# Sensor.net
KiCad netlist of a schematic drawn in Altium Designer
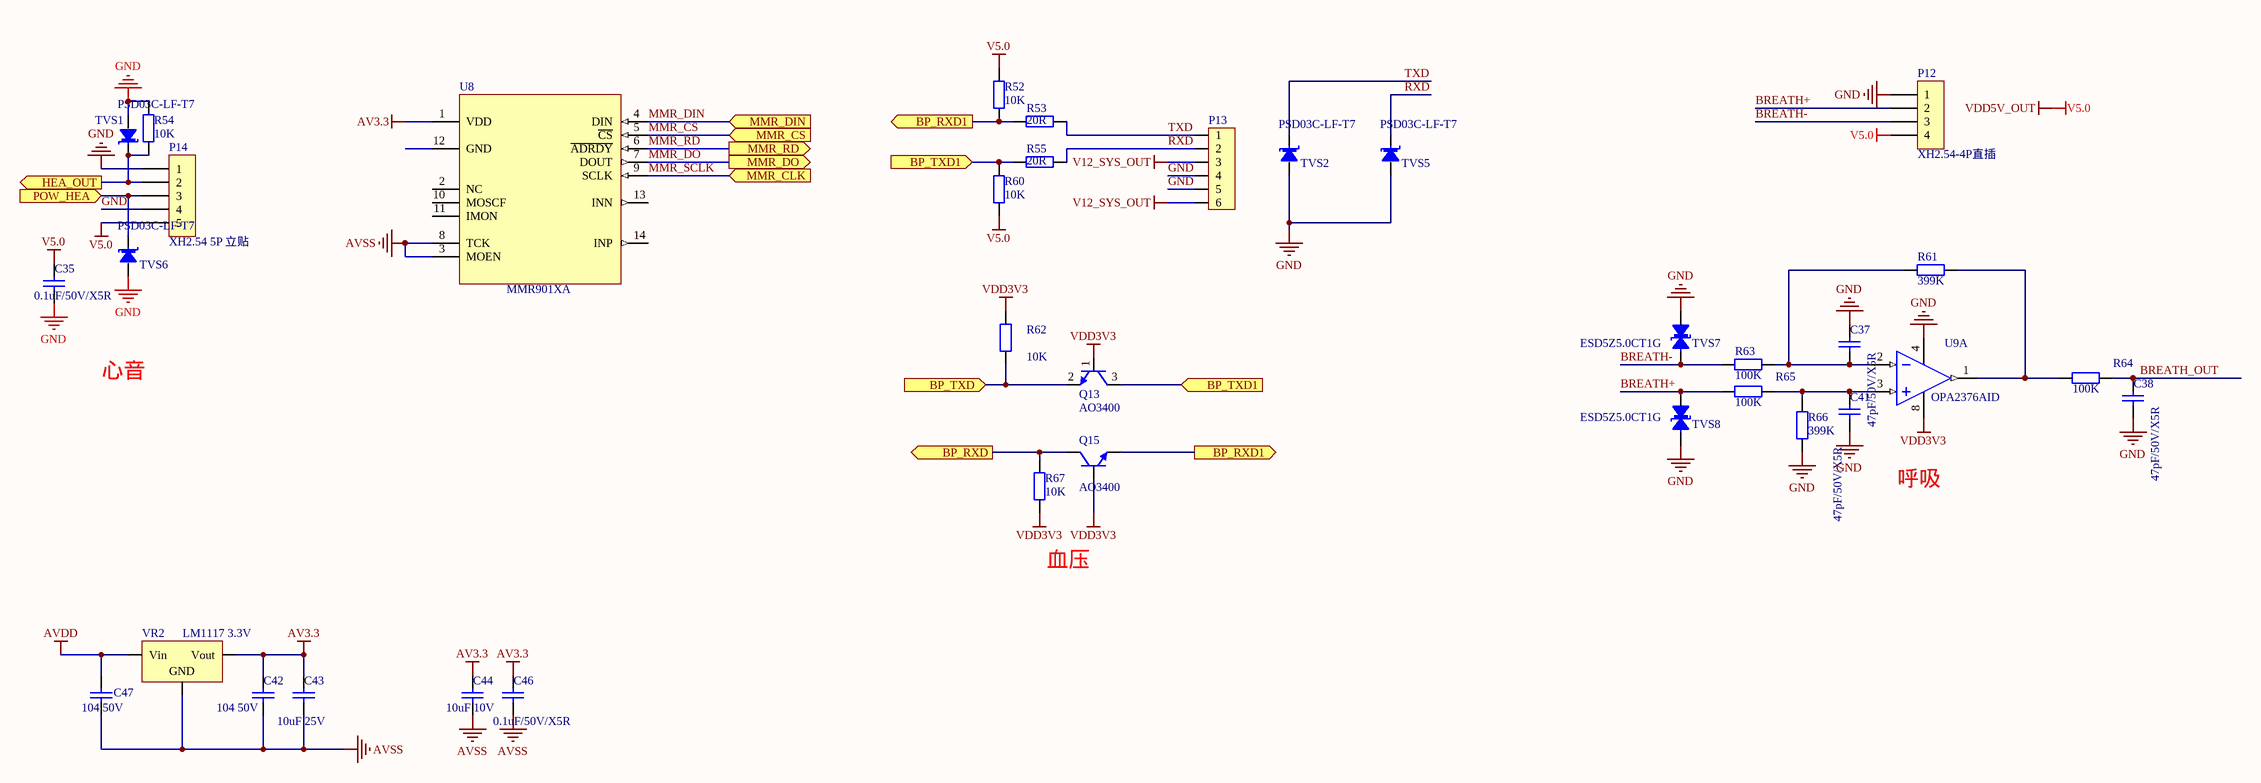
[diagram p0: Sensor.SchDoc]

(export (version "E")
  (design (tool "Eeschema 10.0.6"))
  (components
    (comp (ref "C35")
      (value "0.1uF/50V/X5R")
      (footprint "SMD-0603C")
      (description "贴片电容 20%")
      (libsource (lib "XiaoyI") (part "CAP4"))
    )
    (comp (ref "C37")
      (value "47pF/50V/X5R")
      (footprint "SMD-0603C")
      (description "贴片电容 10%")
      (libsource (lib "XiaoyI") (part "CAP4"))
    )
    (comp (ref "C38")
      (value "47pF/50V/X5R")
      (footprint "SMD-0603C")
      (description "贴片电容 10%")
      (libsource (lib "XiaoyI") (part "CAP4"))
    )
    (comp (ref "C41")
      (value "47pF/50V/X5R")
      (footprint "SMD-0603C")
      (description "贴片电容 10%")
      (libsource (lib "XiaoyI") (part "CAP4"))
    )
    (comp (ref "C42")
      (value "104 50V")
      (footprint "SMD-0603C")
      (description "贴片电容 10%")
      (libsource (lib "XiaoyI") (part "CAP4"))
    )
    (comp (ref "C43")
      (value "10uF 25V")
      (footprint "SMD-0603C")
      (description "贴片电容 20%")
      (libsource (lib "XiaoyI") (part "CAP4"))
    )
    (comp (ref "C44")
      (value "10uF 10V")
      (footprint "SMD-0603C")
      (description "贴片电容 20%")
      (libsource (lib "XiaoyI") (part "CAP4"))
    )
    (comp (ref "C46")
      (value "0.1uF/50V/X5R")
      (footprint "SMD-0603C")
      (description "贴片电容 10%")
      (libsource (lib "XiaoyI") (part "CAP4"))
    )
    (comp (ref "C47")
      (value "104 50V")
      (footprint "SMD-0603C")
      (description "贴片电容 10%")
      (libsource (lib "XiaoyI") (part "CAP4"))
    )
    (comp (ref "P12") (value "XH2.54-4P直插") (footprint "4X2.54MMw") (libsource (lib "ABB") (part "SIP-4")))
    (comp (ref "P13")
      (value "XH2.54 6P 立贴")
      (footprint "6X2.54MMW")
      (description "血压计接口")
      (libsource (lib "ABB") (part "SIP-6"))
    )
    (comp (ref "P14")
      (value "XH2.54 5P 立贴")
      (footprint "5X2.54MMW")
      (description "心音传感器接口")
      (libsource (lib "ABB") (part "SIP-5"))
    )
    (comp (ref "Q13")
      (value "AO3400")
      (footprint "SOT-23")
      (description "NPN")
      (libsource (lib "") (part "NPN-1_1"))
    )
    (comp (ref "Q15")
      (value "AO3400")
      (footprint "SOT-23")
      (description "NPN")
      (libsource (lib "XiaoyI") (part "NPN-1"))
    )
    (comp (ref "R52")
      (value "10K")
      (footprint "SMD-0603")
      (description "贴片电阻 1%")
      (libsource (lib "") (part "RES2_2"))
    )
    (comp (ref "R53")
      (value "20R")
      (footprint "SMD-0603")
      (description "贴片电阻 1%")
      (libsource (lib "XiaoyI") (part "RES2"))
    )
    (comp (ref "R54")
      (value "10K")
      (footprint "SMD-0603")
      (description "贴片电阻 1%")
      (libsource (lib "") (part "RES2_2"))
    )
    (comp (ref "R55")
      (value "20R")
      (footprint "SMD-0603")
      (description "贴片电阻 1%")
      (libsource (lib "XiaoyI") (part "RES2"))
    )
    (comp (ref "R60")
      (value "10K")
      (footprint "SMD-0603")
      (description "贴片电阻 1%")
      (libsource (lib "") (part "RES2_2"))
    )
    (comp (ref "R61")
      (value "399K")
      (footprint "SMD-0603")
      (description "贴片电阻 1%")
      (libsource (lib "") (part "RES2_3"))
    )
    (comp (ref "R62")
      (value "10K")
      (footprint "SMD-0603")
      (description "贴片电阻 1%")
      (libsource (lib "") (part "RES2_1"))
    )
    (comp (ref "R63")
      (value "100K")
      (footprint "SMD-0603")
      (description "贴片电阻 1%")
      (libsource (lib "") (part "RES2_3"))
    )
    (comp (ref "R64")
      (value "100K")
      (footprint "SMD-0603")
      (description "贴片电阻 1%")
      (libsource (lib "") (part "RES2_3"))
    )
    (comp (ref "R65")
      (value "100K")
      (footprint "SMD-0603")
      (description "贴片电阻 1%")
      (libsource (lib "") (part "RES2_3"))
    )
    (comp (ref "R66")
      (value "399K")
      (footprint "SMD-0603")
      (description "贴片电阻 1%")
      (libsource (lib "") (part "RES2_1"))
    )
    (comp (ref "R67")
      (value "10K")
      (footprint "SMD-0603")
      (description "贴片电阻 1%")
      (libsource (lib "") (part "RES2_1"))
    )
    (comp (ref "TVS1")
      (value "PSD03C-LF-T7")
      (footprint "SOD-323")
      (description "单向TVS")
      (libsource (lib "") (part "TVS-S_1"))
    )
    (comp (ref "TVS2")
      (value "PSD03C-LF-T7")
      (footprint "SOD-323")
      (description "单向TVS")
      (libsource (lib "XiaoyI") (part "TVS-S"))
    )
    (comp (ref "TVS5")
      (value "PSD03C-LF-T7")
      (footprint "SOD-323")
      (description "单向TVS")
      (libsource (lib "XiaoyI") (part "TVS-S"))
    )
    (comp (ref "TVS6")
      (value "PSD03C-LF-T7")
      (footprint "SOD-323")
      (description "单向TVS")
      (libsource (lib "XiaoyI") (part "TVS-S"))
    )
    (comp (ref "TVS7")
      (value "ESD5Z5.0CT1G")
      (footprint "SOD-523")
      (description "ESD二极管")
      (libsource (lib "XiaoyI") (part "TVS-1"))
    )
    (comp (ref "TVS8")
      (value "ESD5Z5.0CT1G")
      (footprint "SOD-523")
      (description "ESD二极管")
      (libsource (lib "XiaoyI") (part "TVS-1"))
    )
    (comp (ref "U8")
      (value "MMR901XA")
      (footprint "MMR901XA")
      (description "压力传感器")
      (libsource (lib "XiaoyI") (part "MMR901"))
    )
    (comp (ref "U9")
      (value "OPA2376AID")
      (footprint "SOIC-8")
      (description "运放")
      (libsource (lib "XiaoyI") (part "LM358"))
    )
    (comp (ref "VR2")
      (value "LM1117 3.3V")
      (footprint "SOT223")
      (description "三端稳压器")
      (libsource (lib "XiaoyI") (part "LM1117"))
    )
  )
  (nets
    (net (code "1") (name "/BP_RXD") (class "Default")
      (node (ref "Q15") (pin "3") (pinfunction "C_3") (pintype "passive"))
      (node (ref "R67") (pin "2") (pinfunction "2_2") (pintype "passive"))
    )
    (net (code "2") (name "/BP_RXD1") (class "Default")
      (node (ref "Q15") (pin "2") (pinfunction "E_2") (pintype "passive"))
      (node (ref "R52") (pin "2") (pinfunction "2_2") (pintype "passive"))
      (node (ref "R53") (pin "2") (pinfunction "2_2") (pintype "passive"))
    )
    (net (code "3") (name "/BP_TXD") (class "Default")
      (node (ref "Q13") (pin "2") (pinfunction "E_2") (pintype "passive"))
      (node (ref "R62") (pin "1") (pinfunction "1_1") (pintype "passive"))
    )
    (net (code "4") (name "/BP_TXD1") (class "Default")
      (node (ref "Q13") (pin "3") (pinfunction "C_3") (pintype "passive"))
      (node (ref "R55") (pin "2") (pinfunction "2_2") (pintype "passive"))
      (node (ref "R60") (pin "1") (pinfunction "1_1") (pintype "passive"))
    )
    (net (code "5") (name "/BREATH+") (class "Default")
      (node (ref "P12") (pin "2") (pinfunction "2_2") (pintype "passive"))
      (node (ref "R65") (pin "1") (pinfunction "1_1") (pintype "passive"))
      (node (ref "TVS8") (pin "1") (pinfunction "A_1") (pintype "passive"))
    )
    (net (code "6") (name "/BREATH-") (class "Default")
      (node (ref "P12") (pin "3") (pinfunction "3_3") (pintype "passive"))
      (node (ref "R63") (pin "1") (pinfunction "1_1") (pintype "passive"))
      (node (ref "TVS7") (pin "2") (pinfunction "B_2") (pintype "passive"))
    )
    (net (code "7") (name "/BREATH_OUT") (class "Default")
      (node (ref "C38") (pin "2") (pinfunction "2_2") (pintype "passive"))
      (node (ref "R64") (pin "2") (pinfunction "2_2") (pintype "passive"))
    )
    (net (code "8") (name "/HEA_OUT") (class "Default")
      (node (ref "P14") (pin "2") (pinfunction "2_2") (pintype "passive"))
      (node (ref "R54") (pin "2") (pinfunction "2_2") (pintype "passive"))
      (node (ref "TVS1") (pin "2") (pinfunction "B_2") (pintype "passive"))
    )
    (net (code "9") (name "/MMR_CS") (class "Default")
      (node (ref "U8") (pin "5") (pinfunction "~{CS}_5") (pintype "input"))
    )
    (net (code "10") (name "/MMR_DIN") (class "Default")
      (node (ref "U8") (pin "4") (pinfunction "DIN_4") (pintype "input"))
    )
    (net (code "11") (name "/MMR_DO") (class "Default")
      (node (ref "U8") (pin "7") (pinfunction "DOUT_7") (pintype "output"))
    )
    (net (code "12") (name "/MMR_RD") (class "Default")
      (node (ref "U8") (pin "6") (pinfunction "~{ADRDY}_6") (pintype "input"))
    )
    (net (code "13") (name "/MMR_SCLK") (class "Default")
      (node (ref "U8") (pin "9") (pinfunction "SCLK_9") (pintype "input"))
    )
    (net (code "14") (name "/POW_HEA") (class "Default")
      (node (ref "P14") (pin "3") (pinfunction "3_3") (pintype "passive"))
      (node (ref "TVS6") (pin "2") (pinfunction "B_2") (pintype "passive"))
    )
    (net (code "15") (name "/RXD") (class "Default")
      (node (ref "P13") (pin "2") (pinfunction "2_2") (pintype "passive"))
      (node (ref "R55") (pin "1") (pinfunction "1_1") (pintype "passive"))
      (node (ref "TVS5") (pin "2") (pinfunction "B_2") (pintype "passive"))
    )
    (net (code "16") (name "/TXD") (class "Default")
      (node (ref "P13") (pin "1") (pinfunction "1_1") (pintype "passive"))
      (node (ref "R53") (pin "1") (pinfunction "1_1") (pintype "passive"))
      (node (ref "TVS2") (pin "2") (pinfunction "B_2") (pintype "passive"))
    )
    (net (code "17") (name "AV3.3") (class "Default")
      (node (ref "C42") (pin "2") (pinfunction "2_2") (pintype "passive"))
      (node (ref "C43") (pin "2") (pinfunction "2_2") (pintype "passive"))
      (node (ref "C44") (pin "2") (pinfunction "2_2") (pintype "passive"))
      (node (ref "C46") (pin "2") (pinfunction "2_2") (pintype "passive"))
      (node (ref "U8") (pin "1") (pinfunction "VDD_1") (pintype "power_in"))
      (node (ref "VR2") (pin "2") (pinfunction "Vout_2") (pintype "passive"))
    )
    (net (code "18") (name "AVDD") (class "Default")
      (node (ref "C47") (pin "2") (pinfunction "2_2") (pintype "passive"))
      (node (ref "VR2") (pin "3") (pinfunction "Vin_3") (pintype "passive"))
    )
    (net (code "19") (name "AVSS") (class "Default")
      (node (ref "C42") (pin "1") (pinfunction "1_1") (pintype "passive"))
      (node (ref "C43") (pin "1") (pinfunction "1_1") (pintype "passive"))
      (node (ref "C44") (pin "1") (pinfunction "1_1") (pintype "passive"))
      (node (ref "C46") (pin "1") (pinfunction "1_1") (pintype "passive"))
      (node (ref "C47") (pin "1") (pinfunction "1_1") (pintype "passive"))
      (node (ref "U8") (pin "3") (pinfunction "MOEN_3") (pintype "passive"))
      (node (ref "U8") (pin "8") (pinfunction "TCK_8") (pintype "passive"))
      (node (ref "VR2") (pin "1") (pinfunction "GND_1") (pintype "passive"))
    )
    (net (code "20") (name "GND") (class "Default")
      (node (ref "C35") (pin "1") (pinfunction "1_1") (pintype "passive"))
      (node (ref "C37") (pin "2") (pinfunction "2_2") (pintype "passive"))
      (node (ref "C38") (pin "1") (pinfunction "1_1") (pintype "passive"))
      (node (ref "C41") (pin "1") (pinfunction "1_1") (pintype "passive"))
      (node (ref "P12") (pin "1") (pinfunction "1_1") (pintype "passive"))
      (node (ref "P13") (pin "4") (pinfunction "4_4") (pintype "passive"))
      (node (ref "P13") (pin "5") (pinfunction "5_5") (pintype "passive"))
      (node (ref "P14") (pin "1") (pinfunction "1_1") (pintype "passive"))
      (node (ref "P14") (pin "4") (pinfunction "4_4") (pintype "passive"))
      (node (ref "R54") (pin "1") (pinfunction "1_1") (pintype "passive"))
      (node (ref "R66") (pin "1") (pinfunction "1_1") (pintype "passive"))
      (node (ref "TVS1") (pin "1") (pinfunction "A_1") (pintype "passive"))
      (node (ref "TVS2") (pin "1") (pinfunction "A_1") (pintype "passive"))
      (node (ref "TVS5") (pin "1") (pinfunction "A_1") (pintype "passive"))
      (node (ref "TVS6") (pin "1") (pinfunction "A_1") (pintype "passive"))
      (node (ref "TVS7") (pin "1") (pinfunction "A_1") (pintype "passive"))
      (node (ref "TVS8") (pin "2") (pinfunction "B_2") (pintype "passive"))
      (node (ref "U9") (pin "4") (pinfunction "V-_4") (pintype "power_in"))
    )
    (net (code "21") (name "Net-(U9A-IN1+)") (class "Default")
      (node (ref "C41") (pin "2") (pinfunction "2_2") (pintype "passive"))
      (node (ref "R65") (pin "2") (pinfunction "2_2") (pintype "passive"))
      (node (ref "R66") (pin "2") (pinfunction "2_2") (pintype "passive"))
      (node (ref "U9") (pin "3") (pinfunction "IN1+_3") (pintype "input"))
    )
    (net (code "22") (name "Net-(U9A-IN1-)") (class "Default")
      (node (ref "C37") (pin "1") (pinfunction "1_1") (pintype "passive"))
      (node (ref "R61") (pin "1") (pinfunction "1_1") (pintype "passive"))
      (node (ref "R63") (pin "2") (pinfunction "2_2") (pintype "passive"))
      (node (ref "U9") (pin "2") (pinfunction "IN1-_2") (pintype "input"))
    )
    (net (code "23") (name "Net-(U9A-OUT1)") (class "Default")
      (node (ref "R61") (pin "2") (pinfunction "2_2") (pintype "passive"))
      (node (ref "R64") (pin "1") (pinfunction "1_1") (pintype "passive"))
      (node (ref "U9") (pin "1") (pinfunction "OUT1_1") (pintype "output"))
    )
    (net (code "24") (name "V5.0") (class "Default")
      (node (ref "C35") (pin "2") (pinfunction "2_2") (pintype "passive"))
      (node (ref "P12") (pin "4") (pinfunction "4_4") (pintype "passive"))
      (node (ref "P14") (pin "5") (pinfunction "5_5") (pintype "passive"))
      (node (ref "R52") (pin "1") (pinfunction "1_1") (pintype "passive"))
      (node (ref "R60") (pin "2") (pinfunction "2_2") (pintype "passive"))
    )
    (net (code "25") (name "V12_SYS_OUT") (class "Default")
      (node (ref "P13") (pin "3") (pinfunction "3_3") (pintype "passive"))
      (node (ref "P13") (pin "6") (pinfunction "6_6") (pintype "passive"))
    )
    (net (code "26") (name "VDD3V3") (class "Default")
      (node (ref "Q13") (pin "1") (pinfunction "B_1") (pintype "passive"))
      (node (ref "Q15") (pin "1") (pinfunction "B_1") (pintype "passive"))
      (node (ref "R62") (pin "2") (pinfunction "2_2") (pintype "passive"))
      (node (ref "R67") (pin "1") (pinfunction "1_1") (pintype "passive"))
      (node (ref "U9") (pin "8") (pinfunction "V+_8") (pintype "power_in"))
    )
    (net (code "27") (name "unconnected-(U8-GND-Pad12)") (class "Default")
      (node (ref "U8") (pin "12") (pinfunction "GND_12") (pintype "power_in"))
    )
    (net (code "28") (name "unconnected-(U8-IMON-Pad11)") (class "Default")
      (node (ref "U8") (pin "11") (pinfunction "IMON_11") (pintype "passive"))
    )
    (net (code "29") (name "unconnected-(U8-INN-Pad13)") (class "Default")
      (node (ref "U8") (pin "13") (pinfunction "INN_13") (pintype "output"))
    )
    (net (code "30") (name "unconnected-(U8-INP-Pad14)") (class "Default")
      (node (ref "U8") (pin "14") (pinfunction "INP_14") (pintype "output"))
    )
    (net (code "31") (name "unconnected-(U8-MOSCF-Pad10)") (class "Default")
      (node (ref "U8") (pin "10") (pinfunction "MOSCF_10") (pintype "passive"))
    )
    (net (code "32") (name "unconnected-(U8-NC-Pad2)") (class "Default")
      (node (ref "U8") (pin "2") (pinfunction "NC_2") (pintype "passive"))
    )
  )
)
